# Current_Kill.net
KiCad netlist of a schematic drawn in Altium Designer
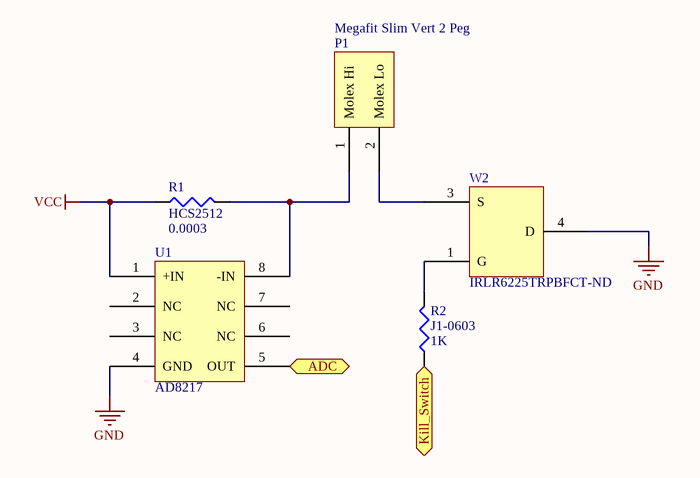
[diagram p0: Current_Kill.SchDoc]

(export (version "E")
  (design (tool "Eeschema 10.0.6"))
  (components
    (comp (ref "P1")
      (value "Megafit Slim Vert 2 Peg")
      (footprint "Molex_DT:76829-0102")
      (fields (field (name "MFGR_PART_NUM") "76829-0102"))
      (libsource (lib "Molex_DT") (part "Megafit Slim Vert 2 Peg"))
    )
    (comp (ref "R1")
      (value "HCS2512")
      (footprint "HCS2512FTL300CT-ND_DT")
      (description "Resistor")
      (fields
        (field (name "ALTIUM_VALUE") "0.0003")
        (field (name "MFGR_PART_NUM") "HCS2512FTL300")
        (field (name "PUBLISHER") "Altium Limited")
      )
      (libsource (lib "Miscellaneous Devices") (part "Res3"))
    )
    (comp (ref "R2")
      (value "J1-0603")
      (footprint "J1-0603")
      (description "Resistor")
      (fields (field (name "ALTIUM_VALUE") "1K") (field (name "PUBLISHER") "Altium Limited"))
      (libsource (lib "Miscellaneous Devices") (part "Res3"))
    )
    (comp (ref "U1")
      (value "AD8217")
      (footprint "AD8217_DT:AD8217_DT")
      (fields (field (name "MFGR_PART_NUM") "AD8217BRMZ-R7"))
      (libsource (lib "AD8217_DT") (part "AD8217"))
    )
    (comp (ref "W2")
      (value "IRLR6225TRPBFCT-ND")
      (footprint "IRLR6225_DT")
      (fields (field (name "MNFR_PART_NUM") "IRLR6225TRPBF"))
      (libsource (lib "IRLR6225_DT") (part "IRLR6225TRPBFCT-ND"))
    )
  )
  (nets
    (net (code "1") (name "/ADC") (class "Default")
      (node (ref "U1") (pin "5") (pinfunction "OUT_5") (pintype "passive"))
    )
    (net (code "2") (name "/Kill_Switch") (class "Default")
      (node (ref "R2") (pin "1") (pinfunction "1_1") (pintype "passive"))
    )
    (net (code "3") (name "GND") (class "Default")
      (node (ref "U1") (pin "4") (pinfunction "GND_4") (pintype "passive"))
      (node (ref "W2") (pin "4") (pinfunction "D_4") (pintype "passive"))
    )
    (net (code "4") (name "Net-(P1-Molex_Hi)") (class "Default")
      (node (ref "P1") (pin "1") (pinfunction "Molex_Hi_1") (pintype "passive"))
      (node (ref "R1") (pin "2") (pinfunction "2_2") (pintype "passive"))
      (node (ref "U1") (pin "8") (pinfunction "-IN_8") (pintype "passive"))
    )
    (net (code "5") (name "Net-(P1-Molex_Lo)") (class "Default")
      (node (ref "P1") (pin "2") (pinfunction "Molex_Lo_2") (pintype "passive"))
      (node (ref "W2") (pin "3") (pinfunction "S_3") (pintype "passive"))
    )
    (net (code "6") (name "Net-(W2-G)") (class "Default")
      (node (ref "R2") (pin "2") (pinfunction "2_2") (pintype "passive"))
      (node (ref "W2") (pin "1") (pinfunction "G_1") (pintype "passive"))
    )
    (net (code "7") (name "VCC") (class "Default")
      (node (ref "R1") (pin "1") (pinfunction "1_1") (pintype "passive"))
      (node (ref "U1") (pin "1") (pinfunction "+IN_1") (pintype "passive"))
    )
    (net (code "8") (name "unconnected-(U1-NC-Pad2)") (class "Default")
      (node (ref "U1") (pin "2") (pinfunction "NC_2") (pintype "passive"))
    )
    (net (code "9") (name "unconnected-(U1-NC-Pad3)") (class "Default")
      (node (ref "U1") (pin "3") (pinfunction "NC_3") (pintype "passive"))
    )
    (net (code "10") (name "unconnected-(U1-NC-Pad6)") (class "Default")
      (node (ref "U1") (pin "6") (pinfunction "NC_6") (pintype "passive"))
    )
    (net (code "11") (name "unconnected-(U1-NC-Pad7)") (class "Default")
      (node (ref "U1") (pin "7") (pinfunction "NC_7") (pintype "passive"))
    )
  )
)
